# Ethernet.net
KiCad netlist of a schematic drawn in Altium Designer
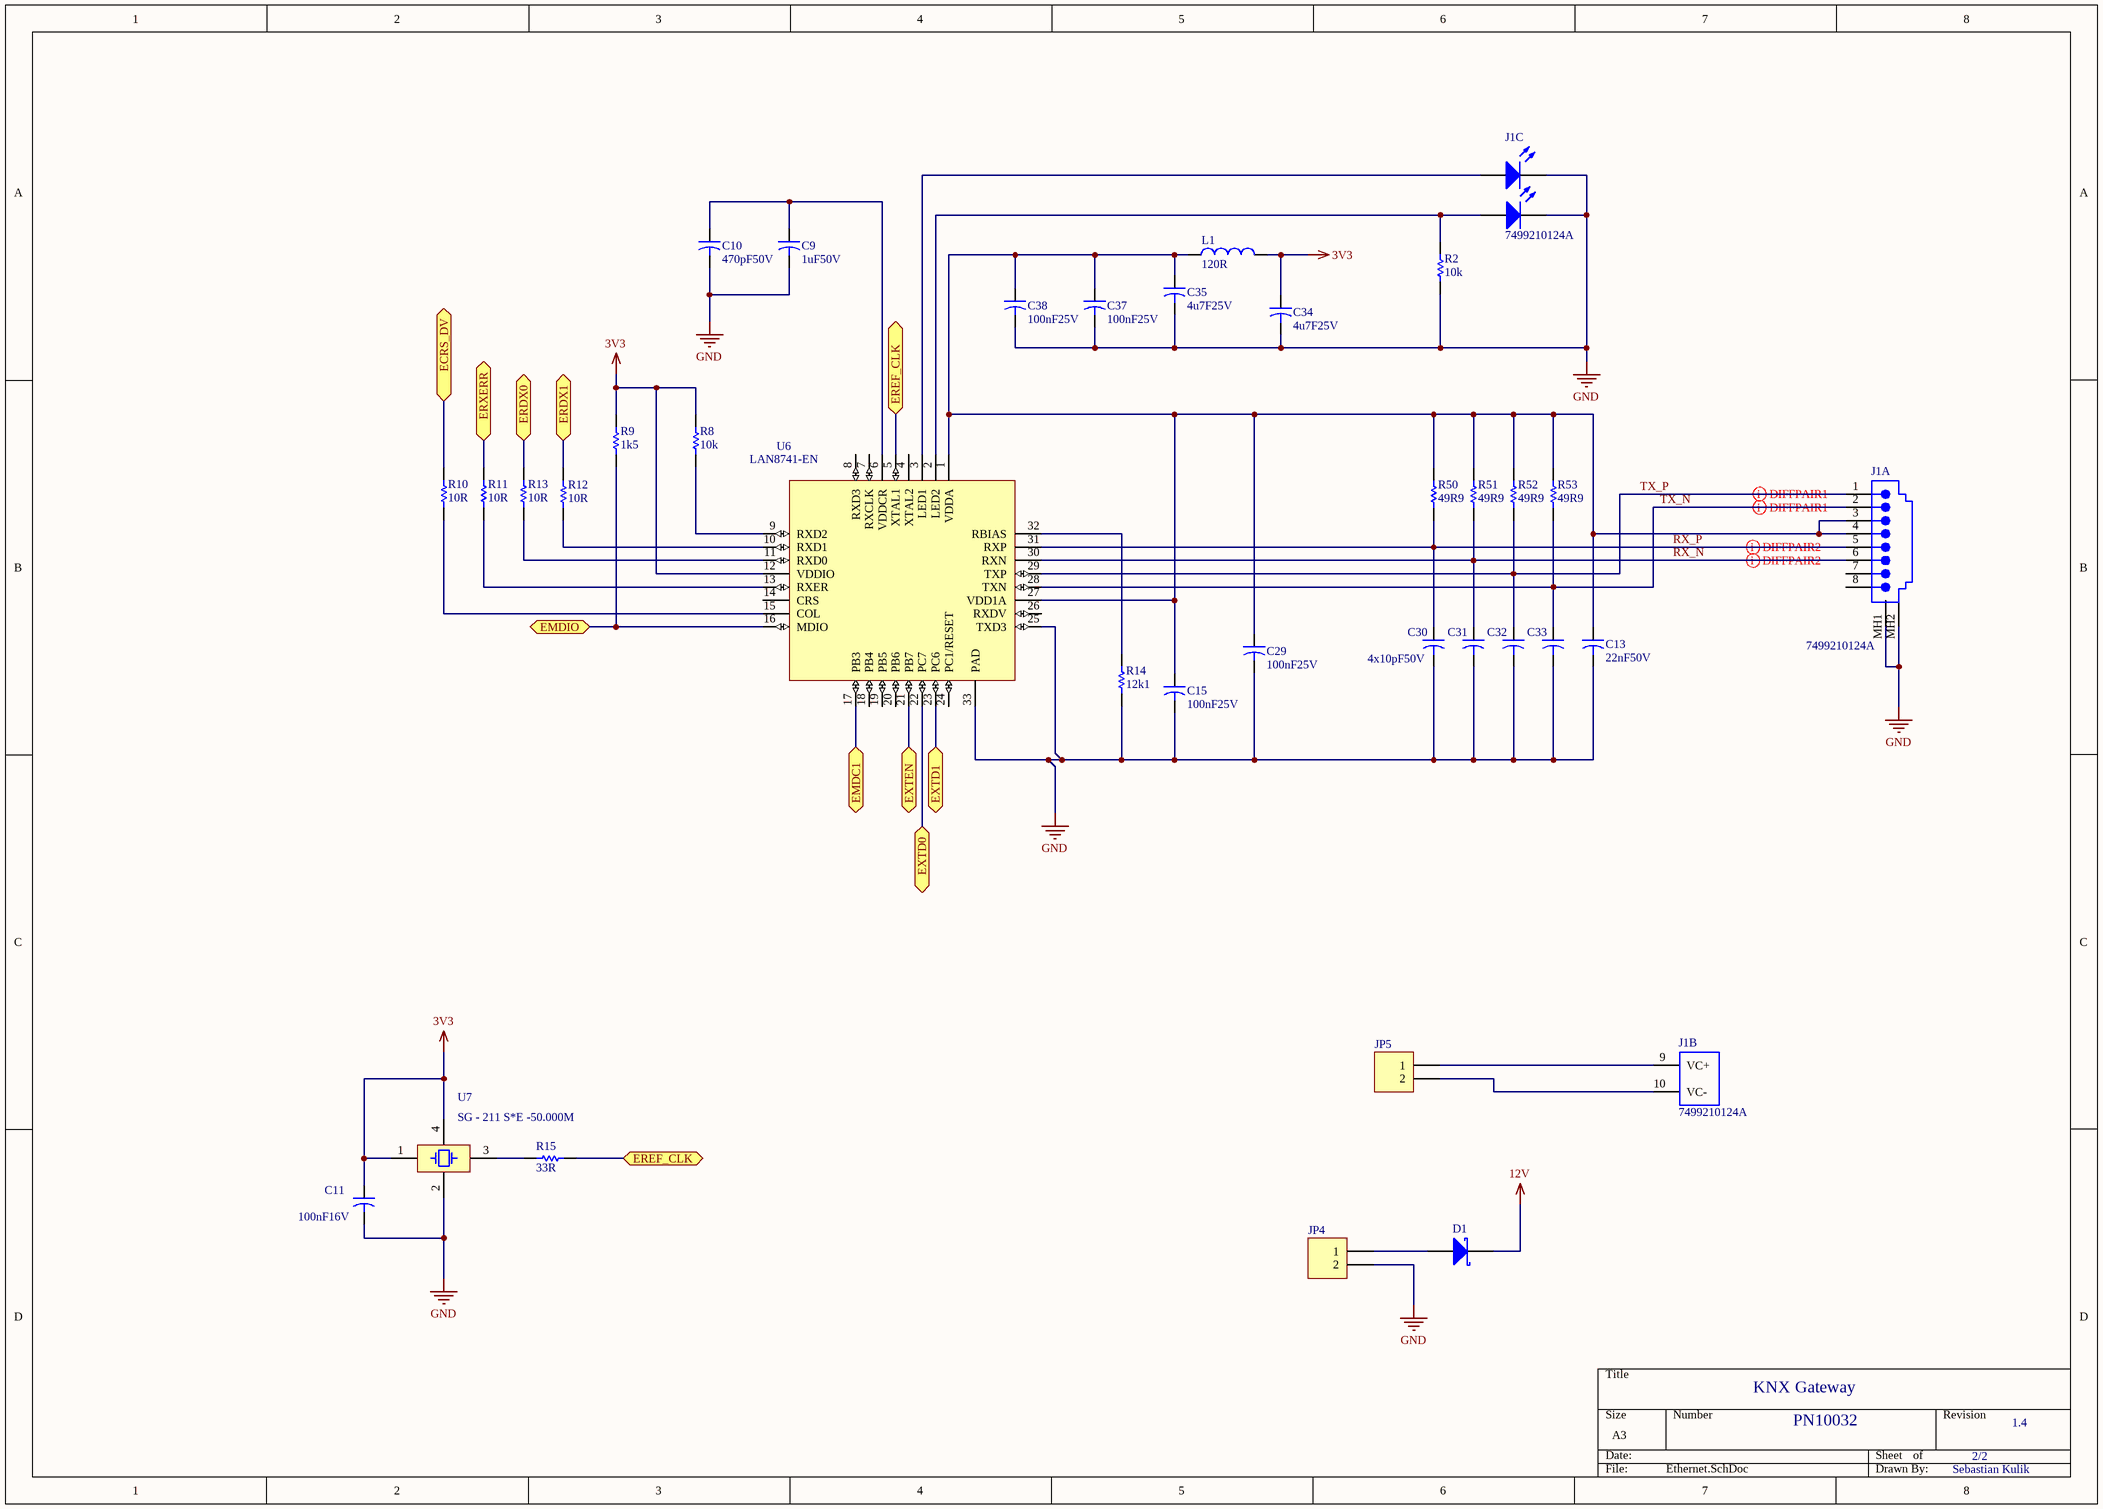
[diagram p0: Ethernet.SchDoc]

(export (version "E")
  (design (tool "Eeschema 10.0.6"))
  (components
    (comp (ref "C9")
      (value "1uF50V")
      (footprint "C0603")
      (description "C series, X5R, 10%")
      (fields
        (field (name "MANUFACTURER") "TDK")
        (field (name "Comment") "1uF50V_0603")
        (field (name "PUBLISHER") "Sebastian Kulik")
      )
      (libsource (lib "Capacitors") (part "1uF50V_0603"))
    )
    (comp (ref "C10")
      (value "470pF50V")
      (footprint "C0402")
      (description "AVX, 50V")
      (fields
        (field (name "MANUFACTURER") "AVX")
        (field (name "Comment") "470pF50V_0402")
        (field (name "PUBLISHER") "Sebastian Kulik")
      )
      (libsource (lib "Capacitors") (part "470pF50V_0402"))
    )
    (comp (ref "C11")
      (value "100nF16V")
      (footprint "C0402")
      (description "Capacitor")
      (fields
        (field (name "MANUFACTURER") "TDK")
        (field (name "Comment") "100nF16V_0402")
        (field (name "PUBLISHER") "Sebastian Kulik")
      )
      (libsource (lib "Capacitors") (part "100nF16V_0402"))
    )
    (comp (ref "C13")
      (value "22nF50V")
      (footprint "C0603")
      (description "AVX ,  X7R, 5%, 50V")
      (fields
        (field (name "MANUFACTURER") "AVX")
        (field (name "Comment") "22nF50V_0603")
        (field (name "PUBLISHER") "Sebastian Kulik")
      )
      (libsource (lib "Capacitors") (part "22nF50V_0603"))
    )
    (comp (ref "C15")
      (value "100nF25V")
      (footprint "C0402")
      (description "AVX, X5R, 10%, 25V")
      (fields
        (field (name "MANUFACTURER") "AVX")
        (field (name "Comment") "100nF25V_0402")
        (field (name "PUBLISHER") "Sebastian Kulik")
      )
      (libsource (lib "Capacitors") (part "100nF25V_0402"))
    )
    (comp (ref "C29")
      (value "100nF25V")
      (footprint "C0402")
      (description "AVX, X5R, 10%, 25V")
      (fields
        (field (name "MANUFACTURER") "AVX")
        (field (name "Comment") "100nF25V_0402")
        (field (name "PUBLISHER") "Sebastian Kulik")
      )
      (libsource (lib "Capacitors") (part "100nF25V_0402"))
    )
    (comp (ref "C30")
      (value "10pF50V_0603")
      (footprint "C0603")
      (description "AVX ,  +-0.5pF, 50V")
      (fields (field (name "MANUFACTURER") "AVX") (field (name "PUBLISHER") "Sebastian Kulik"))
      (libsource (lib "Capacitors") (part "10pF50V_0603"))
    )
    (comp (ref "C31")
      (value "10pF50V_0603")
      (footprint "C0603")
      (description "AVX ,  +-0.5pF, 50V")
      (fields (field (name "MANUFACTURER") "AVX") (field (name "PUBLISHER") "Sebastian Kulik"))
      (libsource (lib "Capacitors") (part "10pF50V_0603"))
    )
    (comp (ref "C32")
      (value "10pF50V_0603")
      (footprint "C0603")
      (description "AVX ,  +-0.5pF, 50V")
      (fields (field (name "MANUFACTURER") "AVX") (field (name "PUBLISHER") "Sebastian Kulik"))
      (libsource (lib "Capacitors") (part "10pF50V_0603"))
    )
    (comp (ref "C33")
      (value "10pF50V_0603")
      (footprint "C0603")
      (description "AVX ,  +-0.5pF, 50V")
      (fields (field (name "MANUFACTURER") "AVX") (field (name "PUBLISHER") "Sebastian Kulik"))
      (libsource (lib "Capacitors") (part "10pF50V_0603"))
    )
    (comp (ref "C34")
      (value "4u7F25V")
      (footprint "C0805")
      (description "TDK  C series, X7R, 10%, 25V")
      (fields
        (field (name "MANUFACTURER") "TDK")
        (field (name "Comment") "4u7F25V_0805")
        (field (name "PUBLISHER") "Sebastian Kulik")
      )
      (libsource (lib "Capacitors") (part "4u7F25V_0805"))
    )
    (comp (ref "C35")
      (value "4u7F25V")
      (footprint "C0805")
      (description "TDK  C series, X7R, 10%, 25V")
      (fields
        (field (name "MANUFACTURER") "TDK")
        (field (name "Comment") "4u7F25V_0805")
        (field (name "PUBLISHER") "Sebastian Kulik")
      )
      (libsource (lib "Capacitors") (part "4u7F25V_0805"))
    )
    (comp (ref "C37")
      (value "100nF25V")
      (footprint "C0402")
      (description "AVX, X5R, 10%, 25V")
      (fields
        (field (name "MANUFACTURER") "AVX")
        (field (name "Comment") "100nF25V_0402")
        (field (name "PUBLISHER") "Sebastian Kulik")
      )
      (libsource (lib "Capacitors") (part "100nF25V_0402"))
    )
    (comp (ref "C38")
      (value "100nF25V")
      (footprint "C0402")
      (description "AVX, X5R, 10%, 25V")
      (fields
        (field (name "MANUFACTURER") "AVX")
        (field (name "Comment") "100nF25V_0402")
        (field (name "PUBLISHER") "Sebastian Kulik")
      )
      (libsource (lib "Capacitors") (part "100nF25V_0402"))
    )
    (comp (ref "D1")
      (value "RB160M-30TR")
      (footprint "SOD123")
      (description "Diode Schottky,2A,40V")
      (fields (field (name "MANUFACTURER") "Rohm") (field (name "PUBLISHER") "Sebastian Kulik"))
      (libsource (lib "Discrete") (part "RB160M-30TR"))
    )
    (comp (ref "J1")
      (value "7499210124A")
      (footprint "7499210124A")
      (description "Modular Jack , Right Angle RJ-45, Low Profile")
      (fields (field (name "MANUFACTURER") "Wuerth Elektronik") (field (name "PUBLISHER") "Sebastian Kulik"))
      (libsource (lib "Connectors") (part "Ethernet, POE, WE7499210124A"))
    )
    (comp (ref "JP4")
      (value "Header-2")
      (footprint "HDR1X2")
      (description "Header, 5-Pin")
      (fields (field (name "PUBLISHER") "Sebastian Kulik"))
      (libsource (lib "Connectors") (part "Header-2"))
    )
    (comp (ref "JP5")
      (value "Header-2")
      (footprint "HDR1X2")
      (description "Header, 5-Pin")
      (fields (field (name "PUBLISHER") "Sebastian Kulik"))
      (libsource (lib "Connectors") (part "Header-2"))
    )
    (comp (ref "L1")
      (value "120R")
      (footprint "L0603")
      (description "Murata, Ferrit, 120Rx2A")
      (fields
        (field (name "MANUFACTURER") "Murata")
        (field (name "Comment") "120R4A_0603")
        (field (name "PUBLISHER") "Sebastian Kulik")
      )
      (libsource (lib "Passives") (part "120R4A_0603"))
    )
    (comp (ref "R2")
      (value "10k")
      (footprint "R0402")
      (description "Vishay CRCW series, 125mW, 1%")
      (fields
        (field (name "MANUFACTURER") "Vishay")
        (field (name "Comment") "10k_0402")
        (field (name "PUBLISHER") "Sebastian Kulik")
      )
      (libsource (lib "Resistors") (part "10k_0402"))
    )
    (comp (ref "R8")
      (value "10k")
      (footprint "R0402")
      (description "Vishay CRCW series, 125mW, 1%")
      (fields
        (field (name "MANUFACTURER") "Vishay")
        (field (name "Comment") "10k_0402")
        (field (name "PUBLISHER") "Sebastian Kulik")
      )
      (libsource (lib "Resistors") (part "10k_0402"))
    )
    (comp (ref "R9")
      (value "1k5")
      (footprint "R0402")
      (description "Vishay CRCW series, 125mW, 1%")
      (fields
        (field (name "MANUFACTURER") "Vishay")
        (field (name "Comment") "1k5_0402")
        (field (name "PUBLISHER") "Sebastian Kulik")
      )
      (libsource (lib "Resistors") (part "1k5_0402"))
    )
    (comp (ref "R10")
      (value "10R")
      (footprint "R0402")
      (description "Vishay CRCW series, 125mW, 1%")
      (fields
        (field (name "MANUFACTURER") "Vishay")
        (field (name "Comment") "10R_0402")
        (field (name "PUBLISHER") "Sebastian Kulik")
      )
      (libsource (lib "Resistors") (part "10R_0402"))
    )
    (comp (ref "R11")
      (value "10R")
      (footprint "R0402")
      (description "Vishay CRCW series, 125mW, 1%")
      (fields
        (field (name "MANUFACTURER") "Vishay")
        (field (name "Comment") "10R_0402")
        (field (name "PUBLISHER") "Sebastian Kulik")
      )
      (libsource (lib "Resistors") (part "10R_0402"))
    )
    (comp (ref "R12")
      (value "10R")
      (footprint "R0402")
      (description "Vishay CRCW series, 125mW, 1%")
      (fields
        (field (name "MANUFACTURER") "Vishay")
        (field (name "Comment") "10R_0402")
        (field (name "PUBLISHER") "Sebastian Kulik")
      )
      (libsource (lib "Resistors") (part "10R_0402"))
    )
    (comp (ref "R13")
      (value "10R")
      (footprint "R0402")
      (description "Vishay CRCW series, 125mW, 1%")
      (fields
        (field (name "MANUFACTURER") "Vishay")
        (field (name "Comment") "10R_0402")
        (field (name "PUBLISHER") "Sebastian Kulik")
      )
      (libsource (lib "Resistors") (part "10R_0402"))
    )
    (comp (ref "R14")
      (value "12k1")
      (footprint "R0603(1608)")
      (description "Vishay, CRCW series, 100mW, 1%")
      (fields
        (field (name "MANUFACTURER") "Vishay")
        (field (name "Comment") "12k1_0603")
        (field (name "PUBLISHER") "Sebastian Kulik")
      )
      (libsource (lib "Resistors") (part "12k1_0603"))
    )
    (comp (ref "R15")
      (value "33R")
      (footprint "R0402")
      (description "Vishay CRCW series, 63mW, 1%")
      (fields
        (field (name "MANUFACTURER") "Vishay")
        (field (name "Comment") "33R_0402")
        (field (name "PUBLISHER") "Sebastian Kulik")
      )
      (libsource (lib "Resistors") (part "33R_0402"))
    )
    (comp (ref "R50")
      (value "49R9")
      (footprint "R0402")
      (description "Vishay CRCW series, 63mW, 1%")
      (fields
        (field (name "MANUFACTURER") "Vishay")
        (field (name "Comment") "49R9_0402")
        (field (name "PUBLISHER") "Sebastian Kulik")
      )
      (libsource (lib "Resistors") (part "49R9_0402"))
    )
    (comp (ref "R51")
      (value "49R9")
      (footprint "R0402")
      (description "Vishay CRCW series, 63mW, 1%")
      (fields
        (field (name "MANUFACTURER") "Vishay")
        (field (name "Comment") "49R9_0402")
        (field (name "PUBLISHER") "Sebastian Kulik")
      )
      (libsource (lib "Resistors") (part "49R9_0402"))
    )
    (comp (ref "R52")
      (value "49R9")
      (footprint "R0402")
      (description "Vishay CRCW series, 63mW, 1%")
      (fields
        (field (name "MANUFACTURER") "Vishay")
        (field (name "Comment") "49R9_0402")
        (field (name "PUBLISHER") "Sebastian Kulik")
      )
      (libsource (lib "Resistors") (part "49R9_0402"))
    )
    (comp (ref "R53")
      (value "49R9")
      (footprint "R0402")
      (description "Vishay CRCW series, 63mW, 1%")
      (fields
        (field (name "MANUFACTURER") "Vishay")
        (field (name "Comment") "49R9_0402")
        (field (name "PUBLISHER") "Sebastian Kulik")
      )
      (libsource (lib "Resistors") (part "49R9_0402"))
    )
    (comp (ref "U6")
      (value "LAN8741-EN")
      (footprint "32M1-A_M")
      (description "Ethernet Phy")
      (fields (field (name "MANUFACTURER") "Microchip") (field (name "PUBLISHER") "Sebastian Kulik"))
      (libsource (lib "ICs") (part "LAN8741-EN"))
    )
    (comp (ref "U7")
      (value "SG - 211 S*E -50.000M")
      (footprint "SG - 211 S*E")
      (description "Crystal")
      (fields (field (name "MANUFACTURER") "Epson") (field (name "PUBLISHER") "Sebastian Kulik"))
      (libsource (lib "ICs") (part "SG - 211 S*E -50.000M"))
    )
  )
  (nets
    (net (code "1") (name "/ECRS_DV") (class "Default")
      (node (ref "R10") (pin "2") (pinfunction "2_2") (pintype "passive"))
    )
    (net (code "2") (name "/EMDC1") (class "Default")
      (node (ref "U6") (pin "17") (pinfunction "PB3_17") (pintype "bidirectional"))
    )
    (net (code "3") (name "/EMDIO") (class "Default")
      (node (ref "R9") (pin "1") (pinfunction "1_1") (pintype "passive"))
      (node (ref "U6") (pin "16") (pinfunction "MDIO_16") (pintype "bidirectional"))
    )
    (net (code "4") (name "/ERDX0") (class "Default")
      (node (ref "R13") (pin "2") (pinfunction "2_2") (pintype "passive"))
    )
    (net (code "5") (name "/ERDX1") (class "Default")
      (node (ref "R12") (pin "1") (pinfunction "1_1") (pintype "passive"))
    )
    (net (code "6") (name "/EREF_CLK") (class "Default")
      (node (ref "R15") (pin "2") (pinfunction "2_2") (pintype "passive"))
      (node (ref "U6") (pin "5") (pinfunction "XTAL1_5") (pintype "bidirectional"))
    )
    (net (code "7") (name "/ERXERR") (class "Default")
      (node (ref "R11") (pin "2") (pinfunction "2_2") (pintype "passive"))
    )
    (net (code "8") (name "/EXTD0") (class "Default")
      (node (ref "U6") (pin "22") (pinfunction "PC7_22") (pintype "bidirectional"))
    )
    (net (code "9") (name "/EXTD1") (class "Default")
      (node (ref "U6") (pin "23") (pinfunction "PC6_23") (pintype "bidirectional"))
    )
    (net (code "10") (name "/EXTEN") (class "Default")
      (node (ref "U6") (pin "21") (pinfunction "PB7_21") (pintype "bidirectional"))
    )
    (net (code "11") (name "/RX_N") (class "Default")
      (node (ref "C31") (pin "1") (pinfunction "1_1") (pintype "passive"))
      (node (ref "J1") (pin "6") (pinfunction "6_6") (pintype "passive"))
      (node (ref "R51") (pin "1") (pinfunction "1_1") (pintype "passive"))
      (node (ref "U6") (pin "30") (pinfunction "RXN_30") (pintype "passive"))
    )
    (net (code "12") (name "/RX_P") (class "Default")
      (node (ref "C30") (pin "1") (pinfunction "1_1") (pintype "passive"))
      (node (ref "J1") (pin "5") (pinfunction "5_5") (pintype "passive"))
      (node (ref "R50") (pin "1") (pinfunction "1_1") (pintype "passive"))
      (node (ref "U6") (pin "31") (pinfunction "RXP_31") (pintype "passive"))
    )
    (net (code "13") (name "/TX_N") (class "Default")
      (node (ref "C33") (pin "1") (pinfunction "1_1") (pintype "passive"))
      (node (ref "J1") (pin "2") (pinfunction "2_2") (pintype "passive"))
      (node (ref "R53") (pin "1") (pinfunction "1_1") (pintype "passive"))
      (node (ref "U6") (pin "28") (pinfunction "TXN_28") (pintype "bidirectional"))
    )
    (net (code "14") (name "/TX_P") (class "Default")
      (node (ref "C32") (pin "1") (pinfunction "1_1") (pintype "passive"))
      (node (ref "J1") (pin "1") (pinfunction "1_1") (pintype "passive"))
      (node (ref "R52") (pin "1") (pinfunction "1_1") (pintype "passive"))
      (node (ref "U6") (pin "29") (pinfunction "TXP_29") (pintype "bidirectional"))
    )
    (net (code "15") (name "3V3") (class "Default")
      (node (ref "C11") (pin "1") (pinfunction "1_1") (pintype "passive"))
      (node (ref "C34") (pin "1") (pinfunction "1_1") (pintype "passive"))
      (node (ref "L1") (pin "2") (pinfunction "2_2") (pintype "passive"))
      (node (ref "R8") (pin "2") (pinfunction "2_2") (pintype "passive"))
      (node (ref "R9") (pin "2") (pinfunction "2_2") (pintype "passive"))
      (node (ref "U6") (pin "12") (pinfunction "VDDIO_12") (pintype "passive"))
      (node (ref "U7") (pin "1") (pinfunction "E/D_1") (pintype "passive"))
      (node (ref "U7") (pin "4") (pinfunction "VCC_4") (pintype "passive"))
    )
    (net (code "16") (name "12V") (class "Default")
      (node (ref "D1") (pin "1") (pinfunction "K_1") (pintype "passive"))
    )
    (net (code "17") (name "GND") (class "Default")
      (node (ref "C10") (pin "2") (pinfunction "2_2") (pintype "passive"))
      (node (ref "C11") (pin "2") (pinfunction "2_2") (pintype "passive"))
      (node (ref "C13") (pin "2") (pinfunction "2_2") (pintype "passive"))
      (node (ref "C15") (pin "2") (pinfunction "2_2") (pintype "passive"))
      (node (ref "C29") (pin "2") (pinfunction "2_2") (pintype "passive"))
      (node (ref "C30") (pin "2") (pinfunction "2_2") (pintype "passive"))
      (node (ref "C31") (pin "2") (pinfunction "2_2") (pintype "passive"))
      (node (ref "C32") (pin "2") (pinfunction "2_2") (pintype "passive"))
      (node (ref "C33") (pin "2") (pinfunction "2_2") (pintype "passive"))
      (node (ref "C34") (pin "2") (pinfunction "2_2") (pintype "passive"))
      (node (ref "C35") (pin "2") (pinfunction "2_2") (pintype "passive"))
      (node (ref "C37") (pin "2") (pinfunction "2_2") (pintype "passive"))
      (node (ref "C38") (pin "2") (pinfunction "2_2") (pintype "passive"))
      (node (ref "C9") (pin "2") (pinfunction "2_2") (pintype "passive"))
      (node (ref "J1") (pin "11") (pinfunction "K_11") (pintype "passive"))
      (node (ref "J1") (pin "13") (pinfunction "K_13") (pintype "passive"))
      (node (ref "J1") (pin "MH1") (pinfunction "Shield_MH1") (pintype "passive"))
      (node (ref "J1") (pin "MH2") (pinfunction "Shield_MH2") (pintype "passive"))
      (node (ref "JP4") (pin "2") (pinfunction "2_2") (pintype "passive"))
      (node (ref "R14") (pin "1") (pinfunction "1_1") (pintype "passive"))
      (node (ref "R2") (pin "1") (pinfunction "1_1") (pintype "passive"))
      (node (ref "U6") (pin "25") (pinfunction "TXD3_25") (pintype "bidirectional"))
      (node (ref "U6") (pin "33") (pinfunction "PAD_33") (pintype "power_in"))
      (node (ref "U7") (pin "2") (pinfunction "GND_2") (pintype "passive"))
    )
    (net (code "18") (name "Net-(D1-A)") (class "Default")
      (node (ref "D1") (pin "2") (pinfunction "A_2") (pintype "passive"))
      (node (ref "JP4") (pin "1") (pinfunction "1_1") (pintype "passive"))
    )
    (net (code "19") (name "Net-(J1B-VC+)") (class "Default")
      (node (ref "J1") (pin "9") (pinfunction "VC+_9") (pintype "passive"))
      (node (ref "JP5") (pin "1") (pinfunction "1_1") (pintype "passive"))
    )
    (net (code "20") (name "Net-(J1B-VC-)") (class "Default")
      (node (ref "J1") (pin "10") (pinfunction "VC-_10") (pintype "passive"))
      (node (ref "JP5") (pin "2") (pinfunction "2_2") (pintype "passive"))
    )
    (net (code "21") (name "Net-(U6-COL)") (class "Default")
      (node (ref "R10") (pin "1") (pinfunction "1_1") (pintype "passive"))
      (node (ref "U6") (pin "15") (pinfunction "COL_15") (pintype "passive"))
    )
    (net (code "22") (name "Net-(U6-LED1)") (class "Default")
      (node (ref "J1") (pin "12") (pinfunction "A_12") (pintype "passive"))
      (node (ref "U6") (pin "3") (pinfunction "LED1_3") (pintype "power_in"))
    )
    (net (code "23") (name "Net-(U6-LED2)") (class "Default")
      (node (ref "J1") (pin "14") (pinfunction "A_14") (pintype "passive"))
      (node (ref "R2") (pin "2") (pinfunction "2_2") (pintype "passive"))
      (node (ref "U6") (pin "2") (pinfunction "LED2_2") (pintype "passive"))
    )
    (net (code "24") (name "Net-(U6-RBIAS)") (class "Default")
      (node (ref "R14") (pin "2") (pinfunction "2_2") (pintype "passive"))
      (node (ref "U6") (pin "32") (pinfunction "RBIAS_32") (pintype "power_in"))
    )
    (net (code "25") (name "Net-(U6-RXD0)") (class "Default")
      (node (ref "R13") (pin "1") (pinfunction "1_1") (pintype "passive"))
      (node (ref "U6") (pin "11") (pinfunction "RXD0_11") (pintype "bidirectional"))
    )
    (net (code "26") (name "Net-(U6-RXD1)") (class "Default")
      (node (ref "R12") (pin "2") (pinfunction "2_2") (pintype "passive"))
      (node (ref "U6") (pin "10") (pinfunction "RXD1_10") (pintype "bidirectional"))
    )
    (net (code "27") (name "Net-(U6-RXD2)") (class "Default")
      (node (ref "R8") (pin "1") (pinfunction "1_1") (pintype "passive"))
      (node (ref "U6") (pin "9") (pinfunction "RXD2_9") (pintype "bidirectional"))
    )
    (net (code "28") (name "Net-(U6-RXER)") (class "Default")
      (node (ref "R11") (pin "1") (pinfunction "1_1") (pintype "passive"))
      (node (ref "U6") (pin "13") (pinfunction "RXER_13") (pintype "bidirectional"))
    )
    (net (code "29") (name "Net-(U6-VDD1A)") (class "Default")
      (node (ref "C13") (pin "1") (pinfunction "1_1") (pintype "passive"))
      (node (ref "C15") (pin "1") (pinfunction "1_1") (pintype "passive"))
      (node (ref "C29") (pin "1") (pinfunction "1_1") (pintype "passive"))
      (node (ref "C35") (pin "1") (pinfunction "1_1") (pintype "passive"))
      (node (ref "C37") (pin "1") (pinfunction "1_1") (pintype "passive"))
      (node (ref "C38") (pin "1") (pinfunction "1_1") (pintype "passive"))
      (node (ref "J1") (pin "3") (pinfunction "3_3") (pintype "passive"))
      (node (ref "J1") (pin "4") (pinfunction "4_4") (pintype "passive"))
      (node (ref "L1") (pin "1") (pinfunction "1_1") (pintype "passive"))
      (node (ref "R50") (pin "2") (pinfunction "2_2") (pintype "passive"))
      (node (ref "R51") (pin "2") (pinfunction "2_2") (pintype "passive"))
      (node (ref "R52") (pin "2") (pinfunction "2_2") (pintype "passive"))
      (node (ref "R53") (pin "2") (pinfunction "2_2") (pintype "passive"))
      (node (ref "U6") (pin "1") (pinfunction "VDDA_1") (pintype "passive"))
      (node (ref "U6") (pin "27") (pinfunction "VDD1A_27") (pintype "passive"))
    )
    (net (code "30") (name "Net-(U6-VDDCR)") (class "Default")
      (node (ref "C10") (pin "1") (pinfunction "1_1") (pintype "passive"))
      (node (ref "C9") (pin "1") (pinfunction "1_1") (pintype "passive"))
      (node (ref "U6") (pin "6") (pinfunction "VDDCR_6") (pintype "passive"))
    )
    (net (code "31") (name "Net-(U7-OSC2)") (class "Default")
      (node (ref "R15") (pin "1") (pinfunction "1_1") (pintype "passive"))
      (node (ref "U7") (pin "3") (pinfunction "OSC2_3") (pintype "passive"))
    )
    (net (code "32") (name "unconnected-(J1-Pad7)") (class "Default")
      (node (ref "J1") (pin "7") (pinfunction "7_7") (pintype "passive"))
    )
    (net (code "33") (name "unconnected-(J1-Pad8)") (class "Default")
      (node (ref "J1") (pin "8") (pinfunction "8_8") (pintype "passive"))
    )
    (net (code "34") (name "unconnected-(U6-CRS-Pad14)") (class "Default")
      (node (ref "U6") (pin "14") (pinfunction "CRS_14") (pintype "passive"))
    )
    (net (code "35") (name "unconnected-(U6-PB4-Pad18)") (class "Default")
      (node (ref "U6") (pin "18") (pinfunction "PB4_18") (pintype "bidirectional"))
    )
    (net (code "36") (name "unconnected-(U6-PB5-Pad19)") (class "Default")
      (node (ref "U6") (pin "19") (pinfunction "PB5_19") (pintype "bidirectional"))
    )
    (net (code "37") (name "unconnected-(U6-PB6-Pad20)") (class "Default")
      (node (ref "U6") (pin "20") (pinfunction "PB6_20") (pintype "bidirectional"))
    )
    (net (code "38") (name "unconnected-(U6-PC1{slash}RESET-Pad24)") (class "Default")
      (node (ref "U6") (pin "24") (pinfunction "PC1/RESET_24") (pintype "bidirectional"))
    )
    (net (code "39") (name "unconnected-(U6-RXCLK-Pad7)") (class "Default")
      (node (ref "U6") (pin "7") (pinfunction "RXCLK_7") (pintype "bidirectional"))
    )
    (net (code "40") (name "unconnected-(U6-RXD3-Pad8)") (class "Default")
      (node (ref "U6") (pin "8") (pinfunction "RXD3_8") (pintype "bidirectional"))
    )
    (net (code "41") (name "unconnected-(U6-RXDV-Pad26)") (class "Default")
      (node (ref "U6") (pin "26") (pinfunction "RXDV_26") (pintype "bidirectional"))
    )
    (net (code "42") (name "unconnected-(U6-XTAL2-Pad4)") (class "Default")
      (node (ref "U6") (pin "4") (pinfunction "XTAL2_4") (pintype "power_in"))
    )
  )
)
